# DistanceSensor.net
KiCad netlist of a schematic drawn in Altium Designer
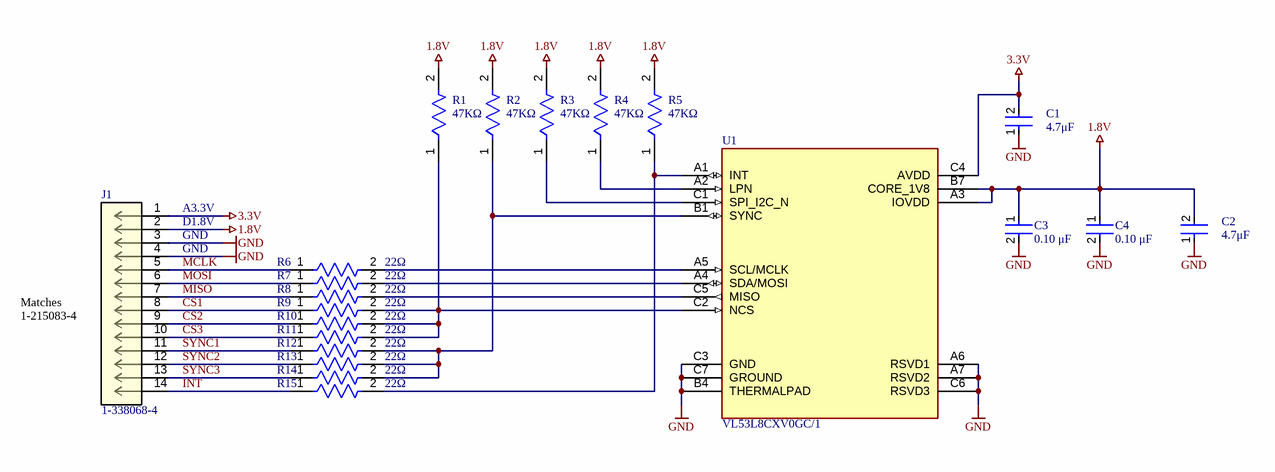
[diagram p0: DistanceSensor.SchDoc]

(export (version "E")
  (design (tool "Eeschema 10.0.6"))
  (components
    (comp (ref "C1")
      (value "GRM188Z71A475ME15D")
      (footprint "FP-GRM188-0_15-IPC_B")
      (description "Chip Multilayer Ceramic Capacitors for General Purpose, 0603, 4.7uF, X7R, 15%, 20%, 10V")
      (fields (field (name "PARAMETER 1") "4.7μF"))
      (libsource (lib "Altium Content Vault") (part "02cd4be3c70576c341d710602a673aa"))
    )
    (comp (ref "C2")
      (value "GRM188Z71A475ME15D")
      (footprint "FP-GRM188-0_15-IPC_B")
      (description "Chip Multilayer Ceramic Capacitors for General Purpose, 0603, 4.7uF, X7R, 15%, 20%, 10V")
      (fields (field (name "PARAMETER 1") "4.7μF"))
      (libsource (lib "Altium Content Vault") (part "02cd4be3c70576c341d710602a673aa"))
    )
    (comp (ref "C3")
      (value "0.10 μF")
      (footprint "FP-C0603C-CF-MFG")
      (description "CAP CER 0.1UF 50V 20% X7R 0603")
      (fields
        (field (name "MANUFACTURER PART NUMBER") "C0603C104M5RACTU")
        (field (name "MANUFACTURER") "KEMET")
      )
      (libsource (lib "Altium Content Vault") (part "b4654b650e69147ec39a6b967a45e02"))
    )
    (comp (ref "C4")
      (value "0.10 μF")
      (footprint "FP-C0603C-CF-MFG")
      (description "CAP CER 0.1UF 50V 20% X7R 0603")
      (fields
        (field (name "MANUFACTURER PART NUMBER") "C0603C104M5RACTU")
        (field (name "MANUFACTURER") "KEMET")
      )
      (libsource (lib "Altium Content Vault") (part "b4654b650e69147ec39a6b967a45e02"))
    )
    (comp (ref "J1")
      (value "1-338068-4")
      (footprint "CONN_1-338068-4_TYC")
      (description "MICRO-MATCH FTE,14P")
      (fields (field (name "COPYRIGHT") "Copyright (C) 2025 Ultra Librarian. All rights reserved."))
      (libsource (lib "robby") (part "1-338068-4"))
    )
    (comp (ref "R1")
      (value "47KΩ")
      (footprint "FP-RT0603-MFG")
      (description "RES 47.0K OHM 1/10W 1% SMD 0603")
      (fields
        (field (name "OCTOPART") "https://octopart.com/rt0603fre0747kl-yageo-40011881")
        (field (name "MANUFACTURER PART NUMBER") "RT0603FRE0747KL")
      )
      (libsource (lib "Altium Content Vault") (part "1029c3af85768c4190bb7ad29bc67b5"))
    )
    (comp (ref "R2")
      (value "47KΩ")
      (footprint "FP-RT0603-MFG")
      (description "RES 47.0K OHM 1/10W 1% SMD 0603")
      (fields
        (field (name "OCTOPART") "https://octopart.com/rt0603fre0747kl-yageo-40011881")
        (field (name "MANUFACTURER PART NUMBER") "RT0603FRE0747KL")
      )
      (libsource (lib "Altium Content Vault") (part "1029c3af85768c4190bb7ad29bc67b5"))
    )
    (comp (ref "R3")
      (value "47KΩ")
      (footprint "FP-RT0603-MFG")
      (description "RES 47.0K OHM 1/10W 1% SMD 0603")
      (fields
        (field (name "OCTOPART") "https://octopart.com/rt0603fre0747kl-yageo-40011881")
        (field (name "MANUFACTURER PART NUMBER") "RT0603FRE0747KL")
      )
      (libsource (lib "Altium Content Vault") (part "1029c3af85768c4190bb7ad29bc67b5"))
    )
    (comp (ref "R4")
      (value "47KΩ")
      (footprint "FP-RT0603-MFG")
      (description "RES 47.0K OHM 1/10W 1% SMD 0603")
      (fields
        (field (name "OCTOPART") "https://octopart.com/rt0603fre0747kl-yageo-40011881")
        (field (name "MANUFACTURER PART NUMBER") "RT0603FRE0747KL")
      )
      (libsource (lib "Altium Content Vault") (part "1029c3af85768c4190bb7ad29bc67b5"))
    )
    (comp (ref "R5")
      (value "47KΩ")
      (footprint "FP-RT0603-MFG")
      (description "RES 47.0K OHM 1/10W 1% SMD 0603")
      (fields
        (field (name "OCTOPART") "https://octopart.com/rt0603fre0747kl-yageo-40011881")
        (field (name "MANUFACTURER PART NUMBER") "RT0603FRE0747KL")
      )
      (libsource (lib "Altium Content Vault") (part "1029c3af85768c4190bb7ad29bc67b5"))
    )
    (comp (ref "R6")
      (value "22Ω")
      (footprint "FP-RT0603-MFG")
      (description "RES SMD 22 OHM 1% 1/10W 0603")
      (fields
        (field (name "MANUFACTURER") "Yageo")
        (field (name "MANUFACTURER PART NUMBER") "RT0603FRE0722RL")
      )
      (libsource (lib "Altium Content Vault") (part "1029c3af85768c4190bb7ad29bc67b5"))
    )
    (comp (ref "R7")
      (value "22Ω")
      (footprint "FP-RT0603-MFG")
      (description "RES SMD 22 OHM 1% 1/10W 0603")
      (fields
        (field (name "MANUFACTURER") "Yageo")
        (field (name "MANUFACTURER PART NUMBER") "RT0603FRE0722RL")
      )
      (libsource (lib "Altium Content Vault") (part "1029c3af85768c4190bb7ad29bc67b5"))
    )
    (comp (ref "R8")
      (value "22Ω")
      (footprint "FP-RT0603-MFG")
      (description "RES SMD 22 OHM 1% 1/10W 0603")
      (fields
        (field (name "MANUFACTURER") "Yageo")
        (field (name "MANUFACTURER PART NUMBER") "RT0603FRE0722RL")
      )
      (libsource (lib "Altium Content Vault") (part "1029c3af85768c4190bb7ad29bc67b5"))
    )
    (comp (ref "R9")
      (value "22Ω")
      (footprint "FP-RT0603-MFG")
      (description "RES SMD 22 OHM 1% 1/10W 0603")
      (fields
        (field (name "MANUFACTURER") "Yageo")
        (field (name "MANUFACTURER PART NUMBER") "RT0603FRE0722RL")
      )
      (libsource (lib "Altium Content Vault") (part "1029c3af85768c4190bb7ad29bc67b5"))
    )
    (comp (ref "R10")
      (value "22Ω")
      (footprint "FP-RT0603-MFG")
      (description "RES SMD 22 OHM 1% 1/10W 0603")
      (fields
        (field (name "MANUFACTURER") "Yageo")
        (field (name "MANUFACTURER PART NUMBER") "RT0603FRE0722RL")
      )
      (libsource (lib "Altium Content Vault") (part "1029c3af85768c4190bb7ad29bc67b5"))
    )
    (comp (ref "R11")
      (value "22Ω")
      (footprint "FP-RT0603-MFG")
      (description "RES SMD 22 OHM 1% 1/10W 0603")
      (fields
        (field (name "MANUFACTURER") "Yageo")
        (field (name "MANUFACTURER PART NUMBER") "RT0603FRE0722RL")
      )
      (libsource (lib "Altium Content Vault") (part "1029c3af85768c4190bb7ad29bc67b5"))
    )
    (comp (ref "R12")
      (value "22Ω")
      (footprint "FP-RT0603-MFG")
      (description "RES SMD 22 OHM 1% 1/10W 0603")
      (fields
        (field (name "MANUFACTURER") "Yageo")
        (field (name "MANUFACTURER PART NUMBER") "RT0603FRE0722RL")
      )
      (libsource (lib "Altium Content Vault") (part "1029c3af85768c4190bb7ad29bc67b5"))
    )
    (comp (ref "R13")
      (value "22Ω")
      (footprint "FP-RT0603-MFG")
      (description "RES SMD 22 OHM 1% 1/10W 0603")
      (fields
        (field (name "MANUFACTURER") "Yageo")
        (field (name "MANUFACTURER PART NUMBER") "RT0603FRE0722RL")
      )
      (libsource (lib "Altium Content Vault") (part "1029c3af85768c4190bb7ad29bc67b5"))
    )
    (comp (ref "R14")
      (value "22Ω")
      (footprint "FP-RT0603-MFG")
      (description "RES SMD 22 OHM 1% 1/10W 0603")
      (fields
        (field (name "MANUFACTURER") "Yageo")
        (field (name "MANUFACTURER PART NUMBER") "RT0603FRE0722RL")
      )
      (libsource (lib "Altium Content Vault") (part "1029c3af85768c4190bb7ad29bc67b5"))
    )
    (comp (ref "R15")
      (value "22Ω")
      (footprint "FP-RT0603-MFG")
      (description "RES SMD 22 OHM 1% 1/10W 0603")
      (fields
        (field (name "MANUFACTURER") "Yageo")
        (field (name "MANUFACTURER PART NUMBER") "RT0603FRE0722RL")
      )
      (libsource (lib "Altium Content Vault") (part "1029c3af85768c4190bb7ad29bc67b5"))
    )
    (comp (ref "U1")
      (value "VL53L8CXV0GC/1")
      (footprint "IC17_LGA16_STM")
      (description "Low-power high-performance 8x8 multizone Time-of-Flight sensor (ToF)")
      (fields (field (name "COPYRIGHT") "Copyright (C) 2025 Ultra Librarian. All rights reserved."))
      (libsource (lib "robby") (part "VL53L8CXV0GC1"))
    )
  )
  (nets
    (net (code "1") (name "/CS1") (class "Default")
      (node (ref "J1") (pin "8") (pinfunction "8_8") (pintype "passive"))
      (node (ref "R9") (pin "1") (pinfunction "1_1") (pintype "passive"))
    )
    (net (code "2") (name "/CS2") (class "Default")
      (node (ref "J1") (pin "9") (pinfunction "9_9") (pintype "passive"))
      (node (ref "R10") (pin "1") (pinfunction "1_1") (pintype "passive"))
    )
    (net (code "3") (name "/CS3") (class "Default")
      (node (ref "J1") (pin "10") (pinfunction "10_10") (pintype "passive"))
      (node (ref "R11") (pin "1") (pinfunction "1_1") (pintype "passive"))
    )
    (net (code "4") (name "/MCLK") (class "Default")
      (node (ref "J1") (pin "5") (pinfunction "5_5") (pintype "passive"))
      (node (ref "R6") (pin "1") (pinfunction "1_1") (pintype "passive"))
    )
    (net (code "5") (name "/MISO") (class "Default")
      (node (ref "J1") (pin "7") (pinfunction "7_7") (pintype "passive"))
      (node (ref "R8") (pin "1") (pinfunction "1_1") (pintype "passive"))
    )
    (net (code "6") (name "/MOSI") (class "Default")
      (node (ref "J1") (pin "6") (pinfunction "6_6") (pintype "passive"))
      (node (ref "R7") (pin "1") (pinfunction "1_1") (pintype "passive"))
    )
    (net (code "7") (name "/SYNC1") (class "Default")
      (node (ref "J1") (pin "11") (pinfunction "11_11") (pintype "passive"))
      (node (ref "R12") (pin "1") (pinfunction "1_1") (pintype "passive"))
    )
    (net (code "8") (name "/SYNC2") (class "Default")
      (node (ref "J1") (pin "12") (pinfunction "12_12") (pintype "passive"))
      (node (ref "R13") (pin "1") (pinfunction "1_1") (pintype "passive"))
    )
    (net (code "9") (name "/SYNC3") (class "Default")
      (node (ref "J1") (pin "13") (pinfunction "13_13") (pintype "passive"))
      (node (ref "R14") (pin "1") (pinfunction "1_1") (pintype "passive"))
    )
    (net (code "10") (name "/~{INT}") (class "Default")
      (node (ref "J1") (pin "14") (pinfunction "14_14") (pintype "passive"))
      (node (ref "R15") (pin "1") (pinfunction "1_1") (pintype "passive"))
    )
    (net (code "11") (name "1.8V") (class "Default")
      (node (ref "C2") (pin "2") (pinfunction "2_2") (pintype "passive"))
      (node (ref "C3") (pin "1") (pinfunction "1_1") (pintype "passive"))
      (node (ref "C4") (pin "1") (pinfunction "1_1") (pintype "passive"))
      (node (ref "J1") (pin "2") (pinfunction "2_2") (pintype "passive"))
      (node (ref "R1") (pin "2") (pinfunction "2_2") (pintype "passive"))
      (node (ref "R2") (pin "2") (pinfunction "2_2") (pintype "passive"))
      (node (ref "R3") (pin "2") (pinfunction "2_2") (pintype "passive"))
      (node (ref "R4") (pin "2") (pinfunction "2_2") (pintype "passive"))
      (node (ref "R5") (pin "2") (pinfunction "2_2") (pintype "passive"))
      (node (ref "U1") (pin "A3") (pinfunction "IOVDD_A3") (pintype "power_in"))
      (node (ref "U1") (pin "B7") (pinfunction "CORE_1V8_B7") (pintype "power_in"))
    )
    (net (code "12") (name "3.3V") (class "Default")
      (node (ref "C1") (pin "2") (pinfunction "2_2") (pintype "passive"))
      (node (ref "J1") (pin "1") (pinfunction "1_1") (pintype "passive"))
      (node (ref "U1") (pin "C4") (pinfunction "AVDD_C4") (pintype "power_in"))
    )
    (net (code "13") (name "GND") (class "Default")
      (node (ref "C1") (pin "1") (pinfunction "1_1") (pintype "passive"))
      (node (ref "C2") (pin "1") (pinfunction "1_1") (pintype "passive"))
      (node (ref "C3") (pin "2") (pinfunction "2_2") (pintype "passive"))
      (node (ref "C4") (pin "2") (pinfunction "2_2") (pintype "passive"))
      (node (ref "J1") (pin "3") (pinfunction "3_3") (pintype "passive"))
      (node (ref "J1") (pin "4") (pinfunction "4_4") (pintype "passive"))
      (node (ref "U1") (pin "A6") (pinfunction "RSVD1_A6") (pintype "passive"))
      (node (ref "U1") (pin "A7") (pinfunction "RSVD2_A7") (pintype "passive"))
      (node (ref "U1") (pin "B4") (pinfunction "THERMALPAD_B4") (pintype "power_in"))
      (node (ref "U1") (pin "C3") (pinfunction "GND_C3") (pintype "power_in"))
      (node (ref "U1") (pin "C6") (pinfunction "RSVD3_C6") (pintype "passive"))
      (node (ref "U1") (pin "C7") (pinfunction "GROUND_C7") (pintype "power_in"))
    )
    (net (code "14") (name "Net-(U1-INT)") (class "Default")
      (node (ref "R15") (pin "2") (pinfunction "2_2") (pintype "passive"))
      (node (ref "R5") (pin "1") (pinfunction "1_1") (pintype "passive"))
      (node (ref "U1") (pin "A1") (pinfunction "INT_A1") (pintype "bidirectional"))
    )
    (net (code "15") (name "Net-(U1-LPN)") (class "Default")
      (node (ref "R4") (pin "1") (pinfunction "1_1") (pintype "passive"))
      (node (ref "U1") (pin "A2") (pinfunction "LPN_A2") (pintype "input"))
    )
    (net (code "16") (name "Net-(U1-MISO)") (class "Default")
      (node (ref "R8") (pin "2") (pinfunction "2_2") (pintype "passive"))
      (node (ref "U1") (pin "C5") (pinfunction "MISO_C5") (pintype "output"))
    )
    (net (code "17") (name "Net-(U1-NCS)") (class "Default")
      (node (ref "R1") (pin "1") (pinfunction "1_1") (pintype "passive"))
      (node (ref "R10") (pin "2") (pinfunction "2_2") (pintype "passive"))
      (node (ref "R11") (pin "2") (pinfunction "2_2") (pintype "passive"))
      (node (ref "R9") (pin "2") (pinfunction "2_2") (pintype "passive"))
      (node (ref "U1") (pin "C2") (pinfunction "NCS_C2") (pintype "input"))
    )
    (net (code "18") (name "Net-(U1-SCL{slash}MCLK)") (class "Default")
      (node (ref "R6") (pin "2") (pinfunction "2_2") (pintype "passive"))
      (node (ref "U1") (pin "A5") (pinfunction "SCL/MCLK_A5") (pintype "input"))
    )
    (net (code "19") (name "Net-(U1-SDA{slash}MOSI)") (class "Default")
      (node (ref "R7") (pin "2") (pinfunction "2_2") (pintype "passive"))
      (node (ref "U1") (pin "A4") (pinfunction "SDA/MOSI_A4") (pintype "bidirectional"))
    )
    (net (code "20") (name "Net-(U1-SPI_I2C_N)") (class "Default")
      (node (ref "R3") (pin "1") (pinfunction "1_1") (pintype "passive"))
      (node (ref "U1") (pin "C1") (pinfunction "SPI_I2C_N_C1") (pintype "input"))
    )
    (net (code "21") (name "Net-(U1-SYNC)") (class "Default")
      (node (ref "R12") (pin "2") (pinfunction "2_2") (pintype "passive"))
      (node (ref "R13") (pin "2") (pinfunction "2_2") (pintype "passive"))
      (node (ref "R14") (pin "2") (pinfunction "2_2") (pintype "passive"))
      (node (ref "R2") (pin "1") (pinfunction "1_1") (pintype "passive"))
      (node (ref "U1") (pin "B1") (pinfunction "SYNC_B1") (pintype "bidirectional"))
    )
  )
)
